# v3_0.net
KiCad netlist of a schematic drawn in EAGLE
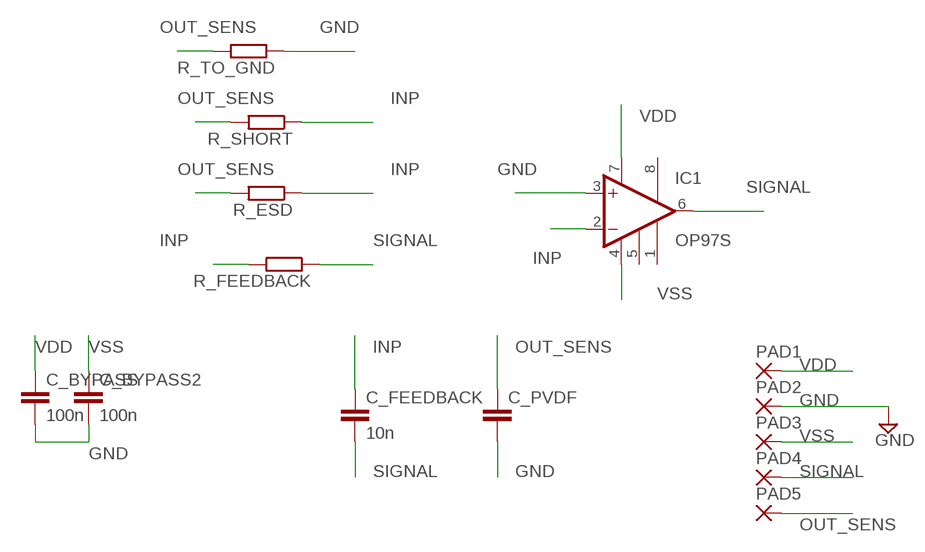
[diagram p0: schematic, sheet 1]

(export (version "E")
  (design (tool "Eeschema 10.0.6"))
  (components
    (comp (ref "C_BYPASS")
      (value "100n")
      (footprint "eagle-import:C0805")
      (libsource (lib "eagle-import") (part "resistor_348_C-EUC0805"))
    )
    (comp (ref "C_BYPASS2")
      (value "100n")
      (footprint "eagle-import:C0805")
      (libsource (lib "eagle-import") (part "resistor_348_C-EUC0805"))
    )
    (comp (ref "C_FEEDBACK")
      (value "10n")
      (footprint "eagle-import:C0805")
      (libsource (lib "eagle-import") (part "C-EUC0805"))
    )
    (comp (ref "C_PVDF")
      (value "C-EUC0805")
      (footprint "eagle-import:C0805")
      (libsource (lib "eagle-import") (part "C-EUC0805"))
    )
    (comp (ref "IC1")
      (value "OP97S")
      (footprint "eagle-import:SO08")
      (libsource (lib "eagle-import") (part "OP97S"))
    )
    (comp (ref "PAD1")
      (value "SMD5")
      (footprint "eagle-import:SMD2,54-5,08")
      (libsource (lib "eagle-import") (part "SMD5"))
    )
    (comp (ref "PAD2")
      (value "SMD5")
      (footprint "eagle-import:SMD2,54-5,08")
      (libsource (lib "eagle-import") (part "SMD5"))
    )
    (comp (ref "PAD3")
      (value "SMD5")
      (footprint "eagle-import:SMD2,54-5,08")
      (libsource (lib "eagle-import") (part "SMD5"))
    )
    (comp (ref "PAD4")
      (value "SMD5")
      (footprint "eagle-import:SMD2,54-5,08")
      (libsource (lib "eagle-import") (part "SMD5"))
    )
    (comp (ref "PAD5")
      (value "SMD5")
      (footprint "eagle-import:SMD2,54-5,08")
      (libsource (lib "eagle-import") (part "SMD5"))
    )
    (comp (ref "R_ESD")
      (value "1M")
      (footprint "eagle-import:M0805")
      (libsource (lib "eagle-import") (part "R-EU_M0805"))
    )
    (comp (ref "R_FEEDBACK")
      (value "100M")
      (footprint "eagle-import:M0805")
      (libsource (lib "eagle-import") (part "R-EU_M0805"))
    )
    (comp (ref "R_SHORT")
      (value "1M")
      (footprint "eagle-import:M0805")
      (libsource (lib "eagle-import") (part "R-EU_M0805"))
    )
    (comp (ref "R_TO_GND")
      (value "1M")
      (footprint "eagle-import:M0805")
      (libsource (lib "eagle-import") (part "R-EU_M0805"))
    )
  )
  (nets
    (net (code "1") (name "/INP") (class "Default")
      (node (ref "C_FEEDBACK") (pin "1") (pinfunction "1_1") (pintype "passive"))
      (node (ref "IC1") (pin "2") (pinfunction "-IN_2") (pintype "input"))
      (node (ref "R_ESD") (pin "1") (pinfunction "1_1") (pintype "passive"))
      (node (ref "R_FEEDBACK") (pin "2") (pinfunction "2_2") (pintype "passive"))
      (node (ref "R_SHORT") (pin "1") (pinfunction "1_1") (pintype "passive"))
    )
    (net (code "2") (name "/OUT_SENS") (class "Default")
      (node (ref "C_PVDF") (pin "1") (pinfunction "1_1") (pintype "passive"))
      (node (ref "PAD5") (pin "1") (pinfunction "P_1") (pintype "passive"))
      (node (ref "R_ESD") (pin "2") (pinfunction "2_2") (pintype "passive"))
      (node (ref "R_SHORT") (pin "2") (pinfunction "2_2") (pintype "passive"))
      (node (ref "R_TO_GND") (pin "2") (pinfunction "2_2") (pintype "passive"))
    )
    (net (code "3") (name "/SIGNAL") (class "Default")
      (node (ref "C_FEEDBACK") (pin "2") (pinfunction "2_2") (pintype "passive"))
      (node (ref "IC1") (pin "6") (pinfunction "OUT_6") (pintype "output"))
      (node (ref "PAD4") (pin "1") (pinfunction "P_1") (pintype "passive"))
      (node (ref "R_FEEDBACK") (pin "1") (pinfunction "1_1") (pintype "passive"))
    )
    (net (code "4") (name "/VDD") (class "Default")
      (node (ref "C_BYPASS") (pin "1") (pinfunction "1_1") (pintype "passive"))
      (node (ref "IC1") (pin "7") (pinfunction "V+_7") (pintype "power_in"))
      (node (ref "PAD1") (pin "1") (pinfunction "P_1") (pintype "passive"))
    )
    (net (code "5") (name "/VSS") (class "Default")
      (node (ref "C_BYPASS2") (pin "1") (pinfunction "1_1") (pintype "passive"))
      (node (ref "IC1") (pin "4") (pinfunction "V-_4") (pintype "power_in"))
      (node (ref "PAD3") (pin "1") (pinfunction "P_1") (pintype "passive"))
    )
    (net (code "6") (name "GND") (class "Default")
      (node (ref "C_BYPASS") (pin "2") (pinfunction "2_2") (pintype "passive"))
      (node (ref "C_BYPASS2") (pin "2") (pinfunction "2_2") (pintype "passive"))
      (node (ref "C_PVDF") (pin "2") (pinfunction "2_2") (pintype "passive"))
      (node (ref "IC1") (pin "3") (pinfunction "+IN_3") (pintype "input"))
      (node (ref "PAD2") (pin "1") (pinfunction "P_1") (pintype "passive"))
      (node (ref "R_TO_GND") (pin "1") (pinfunction "1_1") (pintype "passive"))
    )
    (net (code "7") (name "unconnected-(IC1-BAL1-Pad1)") (class "Default")
      (node (ref "IC1") (pin "1") (pinfunction "BAL1_1") (pintype "passive"))
    )
    (net (code "8") (name "unconnected-(IC1-BAL2-Pad8)") (class "Default")
      (node (ref "IC1") (pin "8") (pinfunction "BAL2_8") (pintype "passive"))
    )
    (net (code "9") (name "unconnected-(IC1-COMP-Pad5)") (class "Default")
      (node (ref "IC1") (pin "5") (pinfunction "COMP_5") (pintype "passive"))
    )
  )
)
